# AC_Plug_Power.net
KiCad netlist of a schematic drawn in Altium Designer
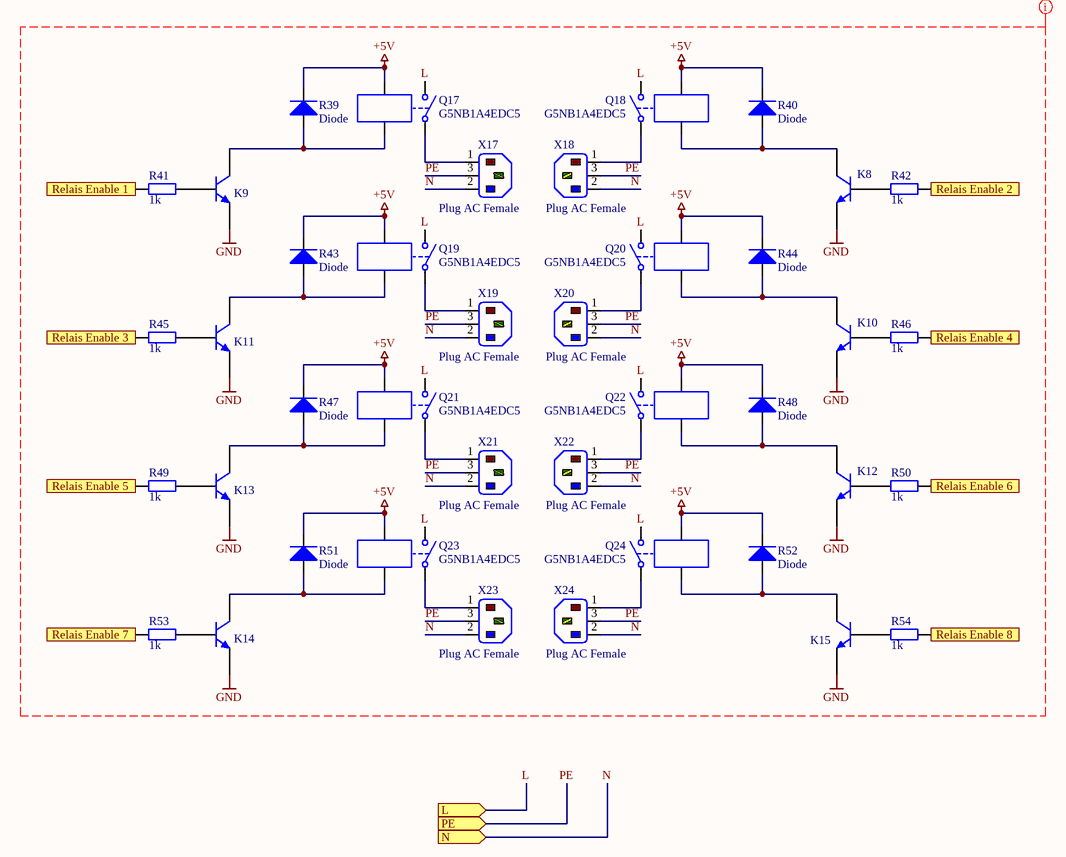
[diagram p0: AC Plug Power.SchDoc]

(export (version "E")
  (design (tool "Eeschema 10.0.6"))
  (components
    (comp (ref "K8")
      (value "BC817-16-7-F")
      (footprint "SOT23-3")
      (description "Transistor NPN in SOT23-3 package")
      (libsource (lib "BBC_Components") (part "BC817-16-7-F"))
    )
    (comp (ref "K9")
      (value "BC817-16-7-F")
      (footprint "SOT23-3")
      (description "Transistor NPN in SOT23-3 package")
      (libsource (lib "BBC_Components") (part "BC817-16-7-F"))
    )
    (comp (ref "K10")
      (value "BC817-16-7-F")
      (footprint "SOT23-3")
      (description "Transistor NPN in SOT23-3 package")
      (libsource (lib "BBC_Components") (part "BC817-16-7-F"))
    )
    (comp (ref "K11")
      (value "BC817-16-7-F")
      (footprint "SOT23-3")
      (description "Transistor NPN in SOT23-3 package")
      (libsource (lib "BBC_Components") (part "BC817-16-7-F"))
    )
    (comp (ref "K12")
      (value "BC817-16-7-F")
      (footprint "SOT23-3")
      (description "Transistor NPN in SOT23-3 package")
      (libsource (lib "BBC_Components") (part "BC817-16-7-F"))
    )
    (comp (ref "K13")
      (value "BC817-16-7-F")
      (footprint "SOT23-3")
      (description "Transistor NPN in SOT23-3 package")
      (libsource (lib "BBC_Components") (part "BC817-16-7-F"))
    )
    (comp (ref "K14")
      (value "BC817-16-7-F")
      (footprint "SOT23-3")
      (description "Transistor NPN in SOT23-3 package")
      (libsource (lib "BBC_Components") (part "BC817-16-7-F"))
    )
    (comp (ref "K15")
      (value "BC817-16-7-F")
      (footprint "SOT23-3")
      (description "Transistor NPN in SOT23-3 package")
      (libsource (lib "BBC_Components") (part "BC817-16-7-F"))
    )
    (comp (ref "Q17")
      (value "G5NB1A4EDC5")
      (footprint "G5NB1A4DC5")
      (description "Single-Pole Single-Throw Relay")
      (fields (field (name "PUBLISHER") "Altium Limited"))
      (libsource (lib "SchematicLibrary") (part "Relay-SPST"))
    )
    (comp (ref "Q18")
      (value "G5NB1A4EDC5")
      (footprint "G5NB1A4DC5")
      (description "Single-Pole Single-Throw Relay")
      (fields (field (name "PUBLISHER") "Altium Limited"))
      (libsource (lib "SchematicLibrary") (part "Relay-SPST"))
    )
    (comp (ref "Q19")
      (value "G5NB1A4EDC5")
      (footprint "G5NB1A4DC5")
      (description "Single-Pole Single-Throw Relay")
      (fields (field (name "PUBLISHER") "Altium Limited"))
      (libsource (lib "SchematicLibrary") (part "Relay-SPST"))
    )
    (comp (ref "Q20")
      (value "G5NB1A4EDC5")
      (footprint "G5NB1A4DC5")
      (description "Single-Pole Single-Throw Relay")
      (fields (field (name "PUBLISHER") "Altium Limited"))
      (libsource (lib "SchematicLibrary") (part "Relay-SPST"))
    )
    (comp (ref "Q21")
      (value "G5NB1A4EDC5")
      (footprint "G5NB1A4DC5")
      (description "Single-Pole Single-Throw Relay")
      (fields (field (name "PUBLISHER") "Altium Limited"))
      (libsource (lib "SchematicLibrary") (part "Relay-SPST"))
    )
    (comp (ref "Q22")
      (value "G5NB1A4EDC5")
      (footprint "G5NB1A4DC5")
      (description "Single-Pole Single-Throw Relay")
      (fields (field (name "PUBLISHER") "Altium Limited"))
      (libsource (lib "SchematicLibrary") (part "Relay-SPST"))
    )
    (comp (ref "Q23")
      (value "G5NB1A4EDC5")
      (footprint "G5NB1A4DC5")
      (description "Single-Pole Single-Throw Relay")
      (fields (field (name "PUBLISHER") "Altium Limited"))
      (libsource (lib "SchematicLibrary") (part "Relay-SPST"))
    )
    (comp (ref "Q24")
      (value "G5NB1A4EDC5")
      (footprint "G5NB1A4DC5")
      (description "Single-Pole Single-Throw Relay")
      (fields (field (name "PUBLISHER") "Altium Limited"))
      (libsource (lib "SchematicLibrary") (part "Relay-SPST"))
    )
    (comp (ref "R39")
      (value "Diode")
      (footprint "DIOMELF3515N")
      (fields (field (name "PUBLISHER") "ICT Berufsbildungscenter AG"))
      (libsource (lib "SchematicLibrary") (part "Diode"))
    )
    (comp (ref "R40")
      (value "Diode")
      (footprint "DIOMELF3515N")
      (fields (field (name "PUBLISHER") "ICT Berufsbildungscenter AG"))
      (libsource (lib "SchematicLibrary") (part "Diode"))
    )
    (comp (ref "R41")
      (value "1k")
      (footprint "RESMELF3514N")
      (description "Resistor")
      (fields (field (name "PUBLISHER") "ICT Berufsbildungscenter AG"))
      (libsource (lib "BBC_Components") (part "Resistor"))
    )
    (comp (ref "R42")
      (value "1k")
      (footprint "RESMELF3514N")
      (description "Resistor")
      (fields (field (name "PUBLISHER") "ICT Berufsbildungscenter AG"))
      (libsource (lib "BBC_Components") (part "Resistor"))
    )
    (comp (ref "R43")
      (value "Diode")
      (footprint "DIOMELF3515N")
      (fields (field (name "PUBLISHER") "ICT Berufsbildungscenter AG"))
      (libsource (lib "SchematicLibrary") (part "Diode"))
    )
    (comp (ref "R44")
      (value "Diode")
      (footprint "DIOMELF3515N")
      (fields (field (name "PUBLISHER") "ICT Berufsbildungscenter AG"))
      (libsource (lib "SchematicLibrary") (part "Diode"))
    )
    (comp (ref "R45")
      (value "1k")
      (footprint "RESMELF3514N")
      (description "Resistor")
      (fields (field (name "PUBLISHER") "ICT Berufsbildungscenter AG"))
      (libsource (lib "BBC_Components") (part "Resistor"))
    )
    (comp (ref "R46")
      (value "1k")
      (footprint "RESMELF3514N")
      (description "Resistor")
      (fields (field (name "PUBLISHER") "ICT Berufsbildungscenter AG"))
      (libsource (lib "BBC_Components") (part "Resistor"))
    )
    (comp (ref "R47")
      (value "Diode")
      (footprint "DIOMELF3515N")
      (fields (field (name "PUBLISHER") "ICT Berufsbildungscenter AG"))
      (libsource (lib "SchematicLibrary") (part "Diode"))
    )
    (comp (ref "R48")
      (value "Diode")
      (footprint "DIOMELF3515N")
      (fields (field (name "PUBLISHER") "ICT Berufsbildungscenter AG"))
      (libsource (lib "SchematicLibrary") (part "Diode"))
    )
    (comp (ref "R49")
      (value "1k")
      (footprint "RESMELF3514N")
      (description "Resistor")
      (fields (field (name "PUBLISHER") "ICT Berufsbildungscenter AG"))
      (libsource (lib "BBC_Components") (part "Resistor"))
    )
    (comp (ref "R50")
      (value "1k")
      (footprint "RESMELF3514N")
      (description "Resistor")
      (fields (field (name "PUBLISHER") "ICT Berufsbildungscenter AG"))
      (libsource (lib "BBC_Components") (part "Resistor"))
    )
    (comp (ref "R51")
      (value "Diode")
      (footprint "DIOMELF3515N")
      (fields (field (name "PUBLISHER") "ICT Berufsbildungscenter AG"))
      (libsource (lib "SchematicLibrary") (part "Diode"))
    )
    (comp (ref "R52")
      (value "Diode")
      (footprint "DIOMELF3515N")
      (fields (field (name "PUBLISHER") "ICT Berufsbildungscenter AG"))
      (libsource (lib "SchematicLibrary") (part "Diode"))
    )
    (comp (ref "R53")
      (value "1k")
      (footprint "RESMELF3514N")
      (description "Resistor")
      (fields (field (name "PUBLISHER") "ICT Berufsbildungscenter AG"))
      (libsource (lib "BBC_Components") (part "Resistor"))
    )
    (comp (ref "R54")
      (value "1k")
      (footprint "RESMELF3514N")
      (description "Resistor")
      (fields (field (name "PUBLISHER") "ICT Berufsbildungscenter AG"))
      (libsource (lib "BBC_Components") (part "Resistor"))
    )
    (comp (ref "X17")
      (value "Plug AC Female")
      (footprint "282841-3")
      (description "IEC Mains Power Inlet, EN60 320-1 C14 Class I Cold Condition, PC Flange Rear Mount, Chassis Plug")
      (fields (field (name "PUBLISHER") "Altium Limited"))
      (libsource (lib "SchematicLibrary") (part "Plug AC Male"))
    )
    (comp (ref "X18")
      (value "Plug AC Female")
      (footprint "282841-3")
      (description "IEC Mains Power Inlet, EN60 320-1 C14 Class I Cold Condition, PC Flange Rear Mount, Chassis Plug")
      (fields (field (name "PUBLISHER") "Altium Limited"))
      (libsource (lib "") (part "Plug AC Male_1"))
    )
    (comp (ref "X19")
      (value "Plug AC Female")
      (footprint "282841-3")
      (description "IEC Mains Power Inlet, EN60 320-1 C14 Class I Cold Condition, PC Flange Rear Mount, Chassis Plug")
      (fields (field (name "PUBLISHER") "Altium Limited"))
      (libsource (lib "SchematicLibrary") (part "Plug AC Male"))
    )
    (comp (ref "X20")
      (value "Plug AC Female")
      (footprint "282841-3")
      (description "IEC Mains Power Inlet, EN60 320-1 C14 Class I Cold Condition, PC Flange Rear Mount, Chassis Plug")
      (fields (field (name "PUBLISHER") "Altium Limited"))
      (libsource (lib "") (part "Plug AC Male_1"))
    )
    (comp (ref "X21")
      (value "Plug AC Female")
      (footprint "282841-3")
      (description "IEC Mains Power Inlet, EN60 320-1 C14 Class I Cold Condition, PC Flange Rear Mount, Chassis Plug")
      (fields (field (name "PUBLISHER") "Altium Limited"))
      (libsource (lib "SchematicLibrary") (part "Plug AC Male"))
    )
    (comp (ref "X22")
      (value "Plug AC Female")
      (footprint "282841-3")
      (description "IEC Mains Power Inlet, EN60 320-1 C14 Class I Cold Condition, PC Flange Rear Mount, Chassis Plug")
      (fields (field (name "PUBLISHER") "Altium Limited"))
      (libsource (lib "") (part "Plug AC Male_1"))
    )
    (comp (ref "X23")
      (value "Plug AC Female")
      (footprint "282841-3")
      (description "IEC Mains Power Inlet, EN60 320-1 C14 Class I Cold Condition, PC Flange Rear Mount, Chassis Plug")
      (fields (field (name "PUBLISHER") "Altium Limited"))
      (libsource (lib "SchematicLibrary") (part "Plug AC Male"))
    )
    (comp (ref "X24")
      (value "Plug AC Female")
      (footprint "282841-3")
      (description "IEC Mains Power Inlet, EN60 320-1 C14 Class I Cold Condition, PC Flange Rear Mount, Chassis Plug")
      (fields (field (name "PUBLISHER") "Altium Limited"))
      (libsource (lib "") (part "Plug AC Male_1"))
    )
  )
  (nets
    (net (code "1") (name "+5V") (class "Default")
      (node (ref "Q17") (pin "4") (pinfunction "4_4") (pintype "passive"))
      (node (ref "Q18") (pin "4") (pinfunction "4_4") (pintype "passive"))
      (node (ref "Q19") (pin "4") (pinfunction "4_4") (pintype "passive"))
      (node (ref "Q20") (pin "4") (pinfunction "4_4") (pintype "passive"))
      (node (ref "Q21") (pin "4") (pinfunction "4_4") (pintype "passive"))
      (node (ref "Q22") (pin "4") (pinfunction "4_4") (pintype "passive"))
      (node (ref "Q23") (pin "4") (pinfunction "4_4") (pintype "passive"))
      (node (ref "Q24") (pin "4") (pinfunction "4_4") (pintype "passive"))
      (node (ref "R39") (pin "C") (pinfunction "Cathode_C") (pintype "passive"))
      (node (ref "R40") (pin "C") (pinfunction "Cathode_C") (pintype "passive"))
      (node (ref "R43") (pin "C") (pinfunction "Cathode_C") (pintype "passive"))
      (node (ref "R44") (pin "C") (pinfunction "Cathode_C") (pintype "passive"))
      (node (ref "R47") (pin "C") (pinfunction "Cathode_C") (pintype "passive"))
      (node (ref "R48") (pin "C") (pinfunction "Cathode_C") (pintype "passive"))
      (node (ref "R51") (pin "C") (pinfunction "Cathode_C") (pintype "passive"))
      (node (ref "R52") (pin "C") (pinfunction "Cathode_C") (pintype "passive"))
    )
    (net (code "2") (name "/L") (class "Default")
      (node (ref "Q17") (pin "2") (pinfunction "2_2") (pintype "passive"))
      (node (ref "Q18") (pin "2") (pinfunction "2_2") (pintype "passive"))
      (node (ref "Q19") (pin "2") (pinfunction "2_2") (pintype "passive"))
      (node (ref "Q20") (pin "2") (pinfunction "2_2") (pintype "passive"))
      (node (ref "Q21") (pin "2") (pinfunction "2_2") (pintype "passive"))
      (node (ref "Q22") (pin "2") (pinfunction "2_2") (pintype "passive"))
      (node (ref "Q23") (pin "2") (pinfunction "2_2") (pintype "passive"))
      (node (ref "Q24") (pin "2") (pinfunction "2_2") (pintype "passive"))
    )
    (net (code "3") (name "/N") (class "Default")
      (node (ref "X17") (pin "2") (pinfunction "N_2") (pintype "passive"))
      (node (ref "X18") (pin "2") (pinfunction "N_2") (pintype "passive"))
      (node (ref "X19") (pin "2") (pinfunction "N_2") (pintype "passive"))
      (node (ref "X20") (pin "2") (pinfunction "N_2") (pintype "passive"))
      (node (ref "X21") (pin "2") (pinfunction "N_2") (pintype "passive"))
      (node (ref "X22") (pin "2") (pinfunction "N_2") (pintype "passive"))
      (node (ref "X23") (pin "2") (pinfunction "N_2") (pintype "passive"))
      (node (ref "X24") (pin "2") (pinfunction "N_2") (pintype "passive"))
    )
    (net (code "4") (name "/PE") (class "Default")
      (node (ref "X17") (pin "3") (pinfunction "E_3") (pintype "passive"))
      (node (ref "X18") (pin "3") (pinfunction "E_3") (pintype "passive"))
      (node (ref "X19") (pin "3") (pinfunction "E_3") (pintype "passive"))
      (node (ref "X20") (pin "3") (pinfunction "E_3") (pintype "passive"))
      (node (ref "X21") (pin "3") (pinfunction "E_3") (pintype "passive"))
      (node (ref "X22") (pin "3") (pinfunction "E_3") (pintype "passive"))
      (node (ref "X23") (pin "3") (pinfunction "E_3") (pintype "passive"))
      (node (ref "X24") (pin "3") (pinfunction "E_3") (pintype "passive"))
    )
    (net (code "5") (name "/Relais Enable 1") (class "Default")
      (node (ref "R41") (pin "1") (pinfunction "1_1") (pintype "passive"))
    )
    (net (code "6") (name "/Relais Enable 2") (class "Default")
      (node (ref "R42") (pin "2") (pinfunction "2_2") (pintype "passive"))
    )
    (net (code "7") (name "/Relais Enable 3") (class "Default")
      (node (ref "R45") (pin "1") (pinfunction "1_1") (pintype "passive"))
    )
    (net (code "8") (name "/Relais Enable 4") (class "Default")
      (node (ref "R46") (pin "2") (pinfunction "2_2") (pintype "passive"))
    )
    (net (code "9") (name "/Relais Enable 5") (class "Default")
      (node (ref "R49") (pin "1") (pinfunction "1_1") (pintype "passive"))
    )
    (net (code "10") (name "/Relais Enable 6") (class "Default")
      (node (ref "R50") (pin "2") (pinfunction "2_2") (pintype "passive"))
    )
    (net (code "11") (name "/Relais Enable 7") (class "Default")
      (node (ref "R53") (pin "1") (pinfunction "1_1") (pintype "passive"))
    )
    (net (code "12") (name "/Relais Enable 8") (class "Default")
      (node (ref "R54") (pin "2") (pinfunction "2_2") (pintype "passive"))
    )
    (net (code "13") (name "GND") (class "Default")
      (node (ref "K10") (pin "2") (pinfunction "E_2") (pintype "passive"))
      (node (ref "K11") (pin "2") (pinfunction "E_2") (pintype "passive"))
      (node (ref "K12") (pin "2") (pinfunction "E_2") (pintype "passive"))
      (node (ref "K13") (pin "2") (pinfunction "E_2") (pintype "passive"))
      (node (ref "K14") (pin "2") (pinfunction "E_2") (pintype "passive"))
      (node (ref "K15") (pin "2") (pinfunction "E_2") (pintype "passive"))
      (node (ref "K8") (pin "2") (pinfunction "E_2") (pintype "passive"))
      (node (ref "K9") (pin "2") (pinfunction "E_2") (pintype "passive"))
    )
    (net (code "14") (name "Net-(K8-B)") (class "Default")
      (node (ref "K8") (pin "1") (pinfunction "B_1") (pintype "passive"))
      (node (ref "R42") (pin "1") (pinfunction "1_1") (pintype "passive"))
    )
    (net (code "15") (name "Net-(K8-C)") (class "Default")
      (node (ref "K8") (pin "3") (pinfunction "C_3") (pintype "passive"))
      (node (ref "Q18") (pin "3") (pinfunction "3_3") (pintype "passive"))
      (node (ref "R40") (pin "A") (pinfunction "Anode_A") (pintype "passive"))
    )
    (net (code "16") (name "Net-(K9-B)") (class "Default")
      (node (ref "K9") (pin "1") (pinfunction "B_1") (pintype "passive"))
      (node (ref "R41") (pin "2") (pinfunction "2_2") (pintype "passive"))
    )
    (net (code "17") (name "Net-(K9-C)") (class "Default")
      (node (ref "K9") (pin "3") (pinfunction "C_3") (pintype "passive"))
      (node (ref "Q17") (pin "3") (pinfunction "3_3") (pintype "passive"))
      (node (ref "R39") (pin "A") (pinfunction "Anode_A") (pintype "passive"))
    )
    (net (code "18") (name "Net-(K10-B)") (class "Default")
      (node (ref "K10") (pin "1") (pinfunction "B_1") (pintype "passive"))
      (node (ref "R46") (pin "1") (pinfunction "1_1") (pintype "passive"))
    )
    (net (code "19") (name "Net-(K10-C)") (class "Default")
      (node (ref "K10") (pin "3") (pinfunction "C_3") (pintype "passive"))
      (node (ref "Q20") (pin "3") (pinfunction "3_3") (pintype "passive"))
      (node (ref "R44") (pin "A") (pinfunction "Anode_A") (pintype "passive"))
    )
    (net (code "20") (name "Net-(K11-B)") (class "Default")
      (node (ref "K11") (pin "1") (pinfunction "B_1") (pintype "passive"))
      (node (ref "R45") (pin "2") (pinfunction "2_2") (pintype "passive"))
    )
    (net (code "21") (name "Net-(K11-C)") (class "Default")
      (node (ref "K11") (pin "3") (pinfunction "C_3") (pintype "passive"))
      (node (ref "Q19") (pin "3") (pinfunction "3_3") (pintype "passive"))
      (node (ref "R43") (pin "A") (pinfunction "Anode_A") (pintype "passive"))
    )
    (net (code "22") (name "Net-(K12-B)") (class "Default")
      (node (ref "K12") (pin "1") (pinfunction "B_1") (pintype "passive"))
      (node (ref "R50") (pin "1") (pinfunction "1_1") (pintype "passive"))
    )
    (net (code "23") (name "Net-(K12-C)") (class "Default")
      (node (ref "K12") (pin "3") (pinfunction "C_3") (pintype "passive"))
      (node (ref "Q22") (pin "3") (pinfunction "3_3") (pintype "passive"))
      (node (ref "R48") (pin "A") (pinfunction "Anode_A") (pintype "passive"))
    )
    (net (code "24") (name "Net-(K13-B)") (class "Default")
      (node (ref "K13") (pin "1") (pinfunction "B_1") (pintype "passive"))
      (node (ref "R49") (pin "2") (pinfunction "2_2") (pintype "passive"))
    )
    (net (code "25") (name "Net-(K13-C)") (class "Default")
      (node (ref "K13") (pin "3") (pinfunction "C_3") (pintype "passive"))
      (node (ref "Q21") (pin "3") (pinfunction "3_3") (pintype "passive"))
      (node (ref "R47") (pin "A") (pinfunction "Anode_A") (pintype "passive"))
    )
    (net (code "26") (name "Net-(K14-B)") (class "Default")
      (node (ref "K14") (pin "1") (pinfunction "B_1") (pintype "passive"))
      (node (ref "R53") (pin "2") (pinfunction "2_2") (pintype "passive"))
    )
    (net (code "27") (name "Net-(K14-C)") (class "Default")
      (node (ref "K14") (pin "3") (pinfunction "C_3") (pintype "passive"))
      (node (ref "Q23") (pin "3") (pinfunction "3_3") (pintype "passive"))
      (node (ref "R51") (pin "A") (pinfunction "Anode_A") (pintype "passive"))
    )
    (net (code "28") (name "Net-(K15-B)") (class "Default")
      (node (ref "K15") (pin "1") (pinfunction "B_1") (pintype "passive"))
      (node (ref "R54") (pin "1") (pinfunction "1_1") (pintype "passive"))
    )
    (net (code "29") (name "Net-(K15-C)") (class "Default")
      (node (ref "K15") (pin "3") (pinfunction "C_3") (pintype "passive"))
      (node (ref "Q24") (pin "3") (pinfunction "3_3") (pintype "passive"))
      (node (ref "R52") (pin "A") (pinfunction "Anode_A") (pintype "passive"))
    )
    (net (code "30") (name "Net-(X17-L)") (class "Default")
      (node (ref "Q17") (pin "1") (pinfunction "1_1") (pintype "passive"))
      (node (ref "X17") (pin "1") (pinfunction "L_1") (pintype "passive"))
    )
    (net (code "31") (name "Net-(X18-L)") (class "Default")
      (node (ref "Q18") (pin "1") (pinfunction "1_1") (pintype "passive"))
      (node (ref "X18") (pin "1") (pinfunction "L_1") (pintype "passive"))
    )
    (net (code "32") (name "Net-(X19-L)") (class "Default")
      (node (ref "Q19") (pin "1") (pinfunction "1_1") (pintype "passive"))
      (node (ref "X19") (pin "1") (pinfunction "L_1") (pintype "passive"))
    )
    (net (code "33") (name "Net-(X20-L)") (class "Default")
      (node (ref "Q20") (pin "1") (pinfunction "1_1") (pintype "passive"))
      (node (ref "X20") (pin "1") (pinfunction "L_1") (pintype "passive"))
    )
    (net (code "34") (name "Net-(X21-L)") (class "Default")
      (node (ref "Q21") (pin "1") (pinfunction "1_1") (pintype "passive"))
      (node (ref "X21") (pin "1") (pinfunction "L_1") (pintype "passive"))
    )
    (net (code "35") (name "Net-(X22-L)") (class "Default")
      (node (ref "Q22") (pin "1") (pinfunction "1_1") (pintype "passive"))
      (node (ref "X22") (pin "1") (pinfunction "L_1") (pintype "passive"))
    )
    (net (code "36") (name "Net-(X23-L)") (class "Default")
      (node (ref "Q23") (pin "1") (pinfunction "1_1") (pintype "passive"))
      (node (ref "X23") (pin "1") (pinfunction "L_1") (pintype "passive"))
    )
    (net (code "37") (name "Net-(X24-L)") (class "Default")
      (node (ref "Q24") (pin "1") (pinfunction "1_1") (pintype "passive"))
      (node (ref "X24") (pin "1") (pinfunction "L_1") (pintype "passive"))
    )
  )
)
